# EEG_Power_Connector_ESP32.net
KiCad netlist of a schematic drawn in Altium Designer
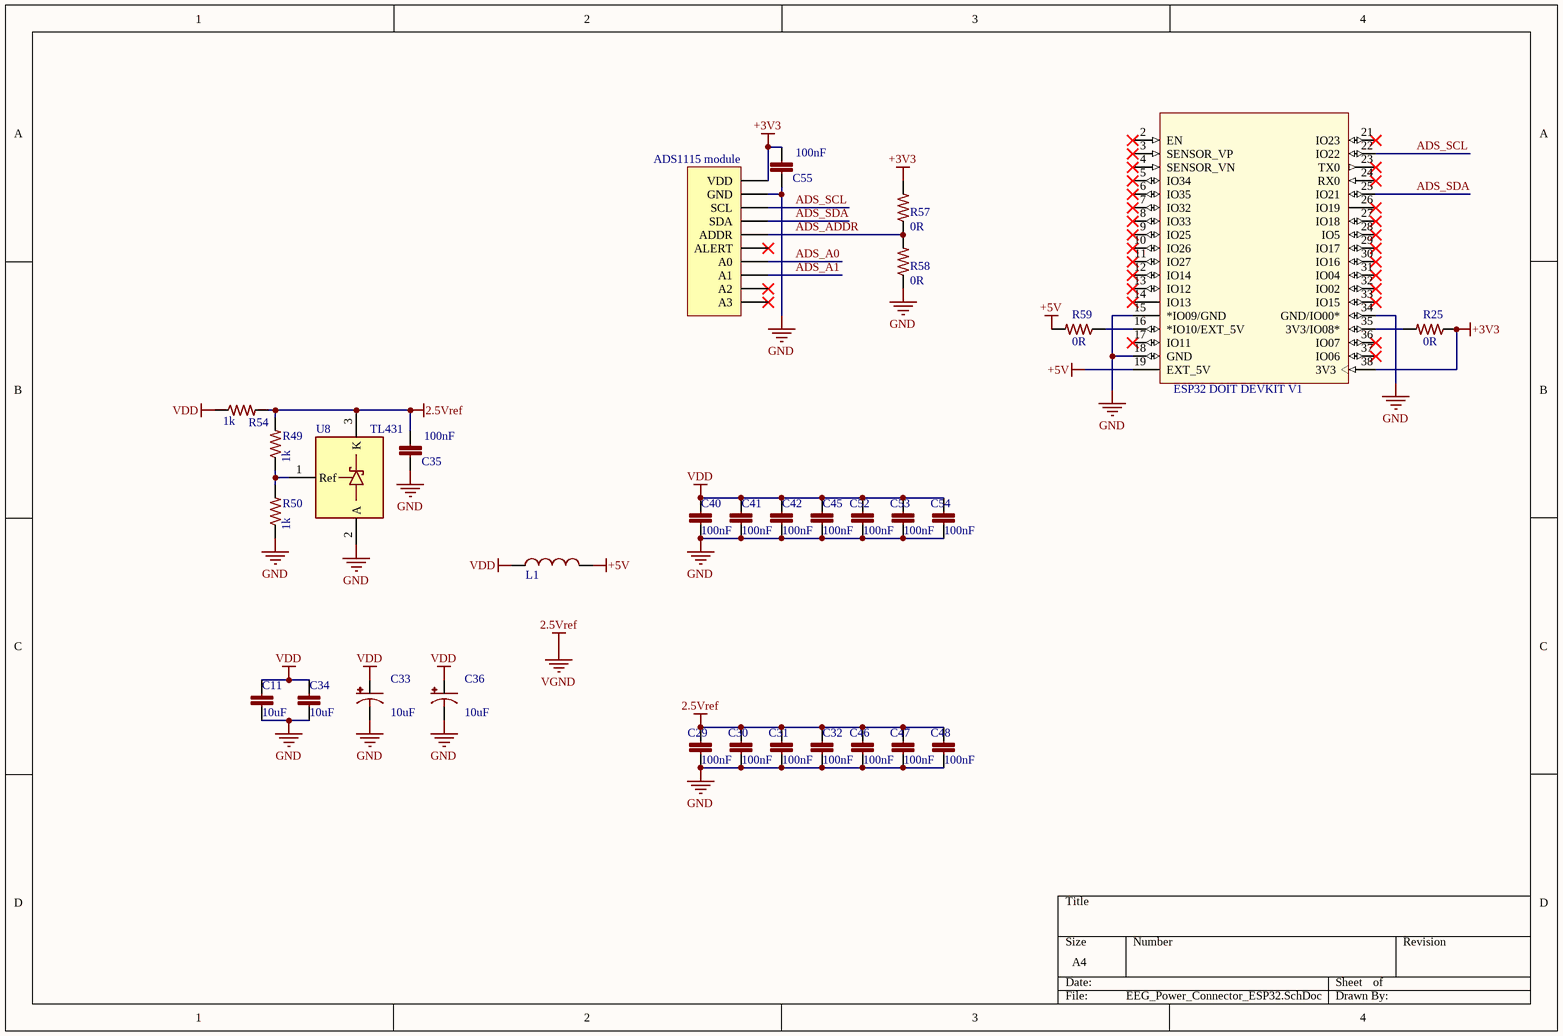
[diagram p0: EEG_Power_Connector_ESP32.SchDoc]

(export (version "E")
  (design (tool "Eeschema 10.0.6"))
  (components
    (comp (ref "A2")
      (value "ESP32 DOIT DEVKIT V1")
      (footprint "MODULE_ESP32-DOIT_DEVKIT-36P")
      (description "EVAL BOARD FOR ESP-WROOM-32")
      (fields (field (name "DIGI-KEY_PART_NUMBER") "1965-1000-ND") (field (name "MP") "ESP32-DEVKITC-32D"))
      (libsource (lib "devkits") (part "ESP32-DEVKITC-38/38P"))
    )
    (comp (ref "A4")
      (value "ADS1115 module")
      (footprint "ADS1115 Module - horizontal")
      (description "16Bit I2C ADC+PGA")
      (libsource (lib "devkits") (part "ADS1115 module"))
    )
    (comp (ref "C11")
      (value "10uF")
      (footprint "C0805 - rounded")
      (description "Generic Capacitor SMD")
      (libsource (lib "rcl") (part "C-EU-SMD"))
    )
    (comp (ref "C29")
      (value "100nF")
      (footprint "C0805 - rounded")
      (description "Generic Capacitor SMD")
      (libsource (lib "rcl") (part "C-EU-SMD"))
    )
    (comp (ref "C30")
      (value "100nF")
      (footprint "C0805 - rounded")
      (description "Generic Capacitor SMD")
      (libsource (lib "rcl") (part "C-EU-SMD"))
    )
    (comp (ref "C31")
      (value "100nF")
      (footprint "C0805 - rounded")
      (description "Generic Capacitor SMD")
      (libsource (lib "rcl") (part "C-EU-SMD"))
    )
    (comp (ref "C32")
      (value "100nF")
      (footprint "C0805 - rounded")
      (description "Generic Capacitor SMD")
      (libsource (lib "rcl") (part "C-EU-SMD"))
    )
    (comp (ref "C33")
      (value "10uF")
      (footprint "E1,8-4")
      (description "Genereric Polarized Capacitor PTH")
      (libsource (lib "rcl") (part "CPOL-US-PTH"))
    )
    (comp (ref "C34")
      (value "10uF")
      (footprint "C0805 - rounded")
      (description "Generic Capacitor SMD")
      (libsource (lib "rcl") (part "C-EU-SMD"))
    )
    (comp (ref "C35")
      (value "100nF")
      (footprint "C0805 - rounded")
      (description "Generic Capacitor SMD")
      (libsource (lib "rcl") (part "C-EU-SMD"))
    )
    (comp (ref "C36")
      (value "10uF")
      (footprint "E1,8-4")
      (description "Genereric Polarized Capacitor PTH")
      (libsource (lib "rcl") (part "CPOL-US-PTH"))
    )
    (comp (ref "C40")
      (value "100nF")
      (footprint "C0805 - rounded")
      (description "Generic Capacitor SMD")
      (libsource (lib "rcl") (part "C-EU-SMD"))
    )
    (comp (ref "C41")
      (value "100nF")
      (footprint "C0805 - rounded")
      (description "Generic Capacitor SMD")
      (libsource (lib "rcl") (part "C-EU-SMD"))
    )
    (comp (ref "C42")
      (value "100nF")
      (footprint "C0805 - rounded")
      (description "Generic Capacitor SMD")
      (libsource (lib "rcl") (part "C-EU-SMD"))
    )
    (comp (ref "C45")
      (value "100nF")
      (footprint "C0805 - rounded")
      (description "Generic Capacitor SMD")
      (libsource (lib "rcl") (part "C-EU-SMD"))
    )
    (comp (ref "C46")
      (value "100nF")
      (footprint "C0805 - rounded")
      (description "Generic Capacitor SMD")
      (libsource (lib "rcl") (part "C-EU-SMD"))
    )
    (comp (ref "C47")
      (value "100nF")
      (footprint "C0805 - rounded")
      (description "Generic Capacitor SMD")
      (libsource (lib "rcl") (part "C-EU-SMD"))
    )
    (comp (ref "C48")
      (value "100nF")
      (footprint "C0805 - rounded")
      (description "Generic Capacitor SMD")
      (libsource (lib "rcl") (part "C-EU-SMD"))
    )
    (comp (ref "C52")
      (value "100nF")
      (footprint "C0805 - rounded")
      (description "Generic Capacitor SMD")
      (libsource (lib "rcl") (part "C-EU-SMD"))
    )
    (comp (ref "C53")
      (value "100nF")
      (footprint "C0805 - rounded")
      (description "Generic Capacitor SMD")
      (libsource (lib "rcl") (part "C-EU-SMD"))
    )
    (comp (ref "C54")
      (value "100nF")
      (footprint "C0805 - rounded")
      (description "Generic Capacitor SMD")
      (libsource (lib "rcl") (part "C-EU-SMD"))
    )
    (comp (ref "C55")
      (value "100nF")
      (footprint "C0805 - rounded")
      (description "Generic Capacitor SMD")
      (libsource (lib "") (part "C-EU-SMD_1"))
    )
    (comp (ref "L1")
      (value "Ferrite bead 0603")
      (footprint "L0805")
      (libsource (lib "rcl") (part "L-US0805"))
    )
    (comp (ref "R25")
      (value "0R")
      (footprint "R0805 - rounded")
      (description "Generic Resistor SMD")
      (libsource (lib "rcl") (part "R-US-SMD"))
    )
    (comp (ref "R49")
      (value "1k")
      (footprint "C0805")
      (description "Generic Resistor SMD")
      (libsource (lib "rcl") (part "R-US-SMD"))
    )
    (comp (ref "R50")
      (value "1k")
      (footprint "C0805")
      (description "Generic Resistor SMD")
      (libsource (lib "rcl") (part "R-US-SMD"))
    )
    (comp (ref "R54")
      (value "1k")
      (footprint "R0805 - rounded")
      (description "Generic Resistor SMD")
      (libsource (lib "rcl") (part "R-US-SMD"))
    )
    (comp (ref "R57")
      (value "0R")
      (footprint "R0805 - rounded")
      (description "Generic Resistor SMD")
      (libsource (lib "rcl") (part "R-US-SMD"))
    )
    (comp (ref "R58")
      (value "0R")
      (footprint "R0805 - rounded")
      (description "Generic Resistor SMD")
      (libsource (lib "rcl") (part "R-US-SMD"))
    )
    (comp (ref "R59")
      (value "0R")
      (footprint "R0805 - rounded")
      (description "Generic Resistor SMD")
      (libsource (lib "rcl") (part "R-US-SMD"))
    )
    (comp (ref "U8")
      (value "TL431")
      (footprint "TO92 - TL431")
      (description "Voltage References Rail Virtual Ground")
      (fields (field (name "PART NUMBER") "TL431"))
      (libsource (lib "Misc") (part "TL431"))
    )
  )
  (nets
    (net (code "1") (name "+3V3") (class "Default")
      (node (ref "A2") (pin "38") (pinfunction "3V3_38") (pintype "input"))
      (node (ref "A4") (pin "1") (pinfunction "VDD_1") (pintype "passive"))
      (node (ref "C55") (pin "1") (pinfunction "1_1") (pintype "passive"))
      (node (ref "R25") (pin "1") (pinfunction "1_1") (pintype "passive"))
      (node (ref "R57") (pin "2") (pinfunction "2_2") (pintype "passive"))
    )
    (net (code "2") (name "+5V") (class "Default")
      (node (ref "A2") (pin "19") (pinfunction "EXT_5V_19") (pintype "power_in"))
      (node (ref "L1") (pin "2") (pinfunction "2_2") (pintype "passive"))
      (node (ref "R59") (pin "2") (pinfunction "2_2") (pintype "passive"))
    )
    (net (code "3") (name "/ADS_A0") (class "Default")
      (node (ref "A4") (pin "7") (pinfunction "A0_7") (pintype "passive"))
    )
    (net (code "4") (name "/ADS_A1") (class "Default")
      (node (ref "A4") (pin "8") (pinfunction "A1_8") (pintype "passive"))
    )
    (net (code "5") (name "/ADS_ADDR") (class "Default")
      (node (ref "A4") (pin "5") (pinfunction "ADDR_5") (pintype "passive"))
      (node (ref "R57") (pin "1") (pinfunction "1_1") (pintype "passive"))
      (node (ref "R58") (pin "2") (pinfunction "2_2") (pintype "passive"))
    )
    (net (code "6") (name "/ADS_SCL") (class "Default")
      (node (ref "A2") (pin "22") (pinfunction "IO22_22") (pintype "bidirectional"))
      (node (ref "A4") (pin "3") (pinfunction "SCL_3") (pintype "passive"))
    )
    (net (code "7") (name "/ADS_SDA") (class "Default")
      (node (ref "A2") (pin "25") (pinfunction "IO21_25") (pintype "bidirectional"))
      (node (ref "A4") (pin "4") (pinfunction "SDA_4") (pintype "passive"))
    )
    (net (code "8") (name "2.5Vref") (class "Default")
      (node (ref "C29") (pin "2") (pinfunction "2_2") (pintype "passive"))
      (node (ref "C30") (pin "2") (pinfunction "2_2") (pintype "passive"))
      (node (ref "C31") (pin "2") (pinfunction "2_2") (pintype "passive"))
      (node (ref "C32") (pin "2") (pinfunction "2_2") (pintype "passive"))
      (node (ref "C35") (pin "2") (pinfunction "2_2") (pintype "passive"))
      (node (ref "C46") (pin "2") (pinfunction "2_2") (pintype "passive"))
      (node (ref "C47") (pin "2") (pinfunction "2_2") (pintype "passive"))
      (node (ref "C48") (pin "2") (pinfunction "2_2") (pintype "passive"))
      (node (ref "R49") (pin "2") (pinfunction "2_2") (pintype "passive"))
      (node (ref "R54") (pin "2") (pinfunction "2_2") (pintype "passive"))
      (node (ref "U8") (pin "3") (pinfunction "K_3") (pintype "passive"))
    )
    (net (code "9") (name "GND") (class "Default")
      (node (ref "A2") (pin "15") (pinfunction "*IO09/GND_15") (pintype "passive"))
      (node (ref "A2") (pin "18") (pinfunction "GND_18") (pintype "bidirectional"))
      (node (ref "A2") (pin "34") (pinfunction "GND/IO00*_34") (pintype "bidirectional"))
      (node (ref "A4") (pin "2") (pinfunction "GND_2") (pintype "passive"))
      (node (ref "C11") (pin "1") (pinfunction "1_1") (pintype "passive"))
      (node (ref "C29") (pin "1") (pinfunction "1_1") (pintype "passive"))
      (node (ref "C30") (pin "1") (pinfunction "1_1") (pintype "passive"))
      (node (ref "C31") (pin "1") (pinfunction "1_1") (pintype "passive"))
      (node (ref "C32") (pin "1") (pinfunction "1_1") (pintype "passive"))
      (node (ref "C33") (pin "-") (pinfunction "-_-") (pintype "passive"))
      (node (ref "C34") (pin "1") (pinfunction "1_1") (pintype "passive"))
      (node (ref "C35") (pin "1") (pinfunction "1_1") (pintype "passive"))
      (node (ref "C36") (pin "-") (pinfunction "-_-") (pintype "passive"))
      (node (ref "C40") (pin "1") (pinfunction "1_1") (pintype "passive"))
      (node (ref "C41") (pin "1") (pinfunction "1_1") (pintype "passive"))
      (node (ref "C42") (pin "1") (pinfunction "1_1") (pintype "passive"))
      (node (ref "C45") (pin "1") (pinfunction "1_1") (pintype "passive"))
      (node (ref "C46") (pin "1") (pinfunction "1_1") (pintype "passive"))
      (node (ref "C47") (pin "1") (pinfunction "1_1") (pintype "passive"))
      (node (ref "C48") (pin "1") (pinfunction "1_1") (pintype "passive"))
      (node (ref "C52") (pin "1") (pinfunction "1_1") (pintype "passive"))
      (node (ref "C53") (pin "1") (pinfunction "1_1") (pintype "passive"))
      (node (ref "C54") (pin "1") (pinfunction "1_1") (pintype "passive"))
      (node (ref "C55") (pin "2") (pinfunction "2_2") (pintype "passive"))
      (node (ref "R50") (pin "1") (pinfunction "1_1") (pintype "passive"))
      (node (ref "R58") (pin "1") (pinfunction "1_1") (pintype "passive"))
      (node (ref "U8") (pin "2") (pinfunction "A_2") (pintype "power_in"))
    )
    (net (code "10") (name "Net-(A2-*IO10{slash}EXT_5V)") (class "Default")
      (node (ref "A2") (pin "16") (pinfunction "*IO10/EXT_5V_16") (pintype "bidirectional"))
      (node (ref "R59") (pin "1") (pinfunction "1_1") (pintype "passive"))
    )
    (net (code "11") (name "Net-(A2-3V3{slash}IO08*)") (class "Default")
      (node (ref "A2") (pin "35") (pinfunction "3V3/IO08*_35") (pintype "bidirectional"))
      (node (ref "R25") (pin "2") (pinfunction "2_2") (pintype "passive"))
    )
    (net (code "12") (name "Net-(U8-Ref)") (class "Default")
      (node (ref "R49") (pin "1") (pinfunction "1_1") (pintype "passive"))
      (node (ref "R50") (pin "2") (pinfunction "2_2") (pintype "passive"))
      (node (ref "U8") (pin "1") (pinfunction "Ref_1") (pintype "power_in"))
    )
    (net (code "13") (name "VDD") (class "Default")
      (node (ref "C11") (pin "2") (pinfunction "2_2") (pintype "passive"))
      (node (ref "C33") (pin "+") (pinfunction "+_+") (pintype "passive"))
      (node (ref "C34") (pin "2") (pinfunction "2_2") (pintype "passive"))
      (node (ref "C36") (pin "+") (pinfunction "+_+") (pintype "passive"))
      (node (ref "C40") (pin "2") (pinfunction "2_2") (pintype "passive"))
      (node (ref "C41") (pin "2") (pinfunction "2_2") (pintype "passive"))
      (node (ref "C42") (pin "2") (pinfunction "2_2") (pintype "passive"))
      (node (ref "C45") (pin "2") (pinfunction "2_2") (pintype "passive"))
      (node (ref "C52") (pin "2") (pinfunction "2_2") (pintype "passive"))
      (node (ref "C53") (pin "2") (pinfunction "2_2") (pintype "passive"))
      (node (ref "C54") (pin "2") (pinfunction "2_2") (pintype "passive"))
      (node (ref "L1") (pin "1") (pinfunction "1_1") (pintype "passive"))
      (node (ref "R54") (pin "1") (pinfunction "1_1") (pintype "passive"))
    )
    (net (code "14") (name "unconnected-(A2-EN-Pad2)") (class "Default")
      (node (ref "A2") (pin "2") (pinfunction "EN_2") (pintype "input+no_connect"))
    )
    (net (code "15") (name "unconnected-(A2-IO02-Pad32)") (class "Default")
      (node (ref "A2") (pin "32") (pinfunction "IO02_32") (pintype "bidirectional+no_connect"))
    )
    (net (code "16") (name "unconnected-(A2-IO04-Pad31)") (class "Default")
      (node (ref "A2") (pin "31") (pinfunction "IO04_31") (pintype "bidirectional+no_connect"))
    )
    (net (code "17") (name "unconnected-(A2-IO5-Pad28)") (class "Default")
      (node (ref "A2") (pin "28") (pinfunction "IO5_28") (pintype "bidirectional+no_connect"))
    )
    (net (code "18") (name "unconnected-(A2-IO06-Pad37)") (class "Default")
      (node (ref "A2") (pin "37") (pinfunction "IO06_37") (pintype "bidirectional+no_connect"))
    )
    (net (code "19") (name "unconnected-(A2-IO07-Pad36)") (class "Default")
      (node (ref "A2") (pin "36") (pinfunction "IO07_36") (pintype "bidirectional+no_connect"))
    )
    (net (code "20") (name "unconnected-(A2-IO11-Pad17)") (class "Default")
      (node (ref "A2") (pin "17") (pinfunction "IO11_17") (pintype "bidirectional+no_connect"))
    )
    (net (code "21") (name "unconnected-(A2-IO12-Pad13)") (class "Default")
      (node (ref "A2") (pin "13") (pinfunction "IO12_13") (pintype "bidirectional+no_connect"))
    )
    (net (code "22") (name "unconnected-(A2-IO13-Pad14)") (class "Default")
      (node (ref "A2") (pin "14") (pinfunction "IO13_14") (pintype "power_in+no_connect"))
    )
    (net (code "23") (name "unconnected-(A2-IO14-Pad12)") (class "Default")
      (node (ref "A2") (pin "12") (pinfunction "IO14_12") (pintype "bidirectional+no_connect"))
    )
    (net (code "24") (name "unconnected-(A2-IO15-Pad33)") (class "Default")
      (node (ref "A2") (pin "33") (pinfunction "IO15_33") (pintype "bidirectional+no_connect"))
    )
    (net (code "25") (name "unconnected-(A2-IO16-Pad30)") (class "Default")
      (node (ref "A2") (pin "30") (pinfunction "IO16_30") (pintype "bidirectional+no_connect"))
    )
    (net (code "26") (name "unconnected-(A2-IO17-Pad29)") (class "Default")
      (node (ref "A2") (pin "29") (pinfunction "IO17_29") (pintype "bidirectional+no_connect"))
    )
    (net (code "27") (name "unconnected-(A2-IO18-Pad27)") (class "Default")
      (node (ref "A2") (pin "27") (pinfunction "IO18_27") (pintype "bidirectional+no_connect"))
    )
    (net (code "28") (name "unconnected-(A2-IO19-Pad26)") (class "Default")
      (node (ref "A2") (pin "26") (pinfunction "IO19_26") (pintype "power_in+no_connect"))
    )
    (net (code "29") (name "unconnected-(A2-IO23-Pad21)") (class "Default")
      (node (ref "A2") (pin "21") (pinfunction "IO23_21") (pintype "bidirectional+no_connect"))
    )
    (net (code "30") (name "unconnected-(A2-IO25-Pad9)") (class "Default")
      (node (ref "A2") (pin "9") (pinfunction "IO25_9") (pintype "bidirectional+no_connect"))
    )
    (net (code "31") (name "unconnected-(A2-IO26-Pad10)") (class "Default")
      (node (ref "A2") (pin "10") (pinfunction "IO26_10") (pintype "bidirectional+no_connect"))
    )
    (net (code "32") (name "unconnected-(A2-IO27-Pad11)") (class "Default")
      (node (ref "A2") (pin "11") (pinfunction "IO27_11") (pintype "bidirectional+no_connect"))
    )
    (net (code "33") (name "unconnected-(A2-IO32-Pad7)") (class "Default")
      (node (ref "A2") (pin "7") (pinfunction "IO32_7") (pintype "bidirectional+no_connect"))
    )
    (net (code "34") (name "unconnected-(A2-IO33-Pad8)") (class "Default")
      (node (ref "A2") (pin "8") (pinfunction "IO33_8") (pintype "bidirectional+no_connect"))
    )
    (net (code "35") (name "unconnected-(A2-IO34-Pad5)") (class "Default")
      (node (ref "A2") (pin "5") (pinfunction "IO34_5") (pintype "bidirectional+no_connect"))
    )
    (net (code "36") (name "unconnected-(A2-IO35-Pad6)") (class "Default")
      (node (ref "A2") (pin "6") (pinfunction "IO35_6") (pintype "bidirectional+no_connect"))
    )
    (net (code "37") (name "unconnected-(A2-RX0-Pad24)") (class "Default")
      (node (ref "A2") (pin "24") (pinfunction "RX0_24") (pintype "input+no_connect"))
    )
    (net (code "38") (name "unconnected-(A2-SENSOR_VN-Pad4)") (class "Default")
      (node (ref "A2") (pin "4") (pinfunction "SENSOR_VN_4") (pintype "input+no_connect"))
    )
    (net (code "39") (name "unconnected-(A2-SENSOR_VP-Pad3)") (class "Default")
      (node (ref "A2") (pin "3") (pinfunction "SENSOR_VP_3") (pintype "input+no_connect"))
    )
    (net (code "40") (name "unconnected-(A2-TX0-Pad23)") (class "Default")
      (node (ref "A2") (pin "23") (pinfunction "TX0_23") (pintype "output+no_connect"))
    )
    (net (code "41") (name "unconnected-(A4-A2-Pad9)") (class "Default")
      (node (ref "A4") (pin "9") (pinfunction "A2_9") (pintype "passive+no_connect"))
    )
    (net (code "42") (name "unconnected-(A4-A3-Pad10)") (class "Default")
      (node (ref "A4") (pin "10") (pinfunction "A3_10") (pintype "passive+no_connect"))
    )
    (net (code "43") (name "unconnected-(A4-ALERT-Pad6)") (class "Default")
      (node (ref "A4") (pin "6") (pinfunction "ALERT_6") (pintype "passive+no_connect"))
    )
  )
)
